# DP0507-1A0.net
KiCad netlist of a schematic drawn in Altium Designer
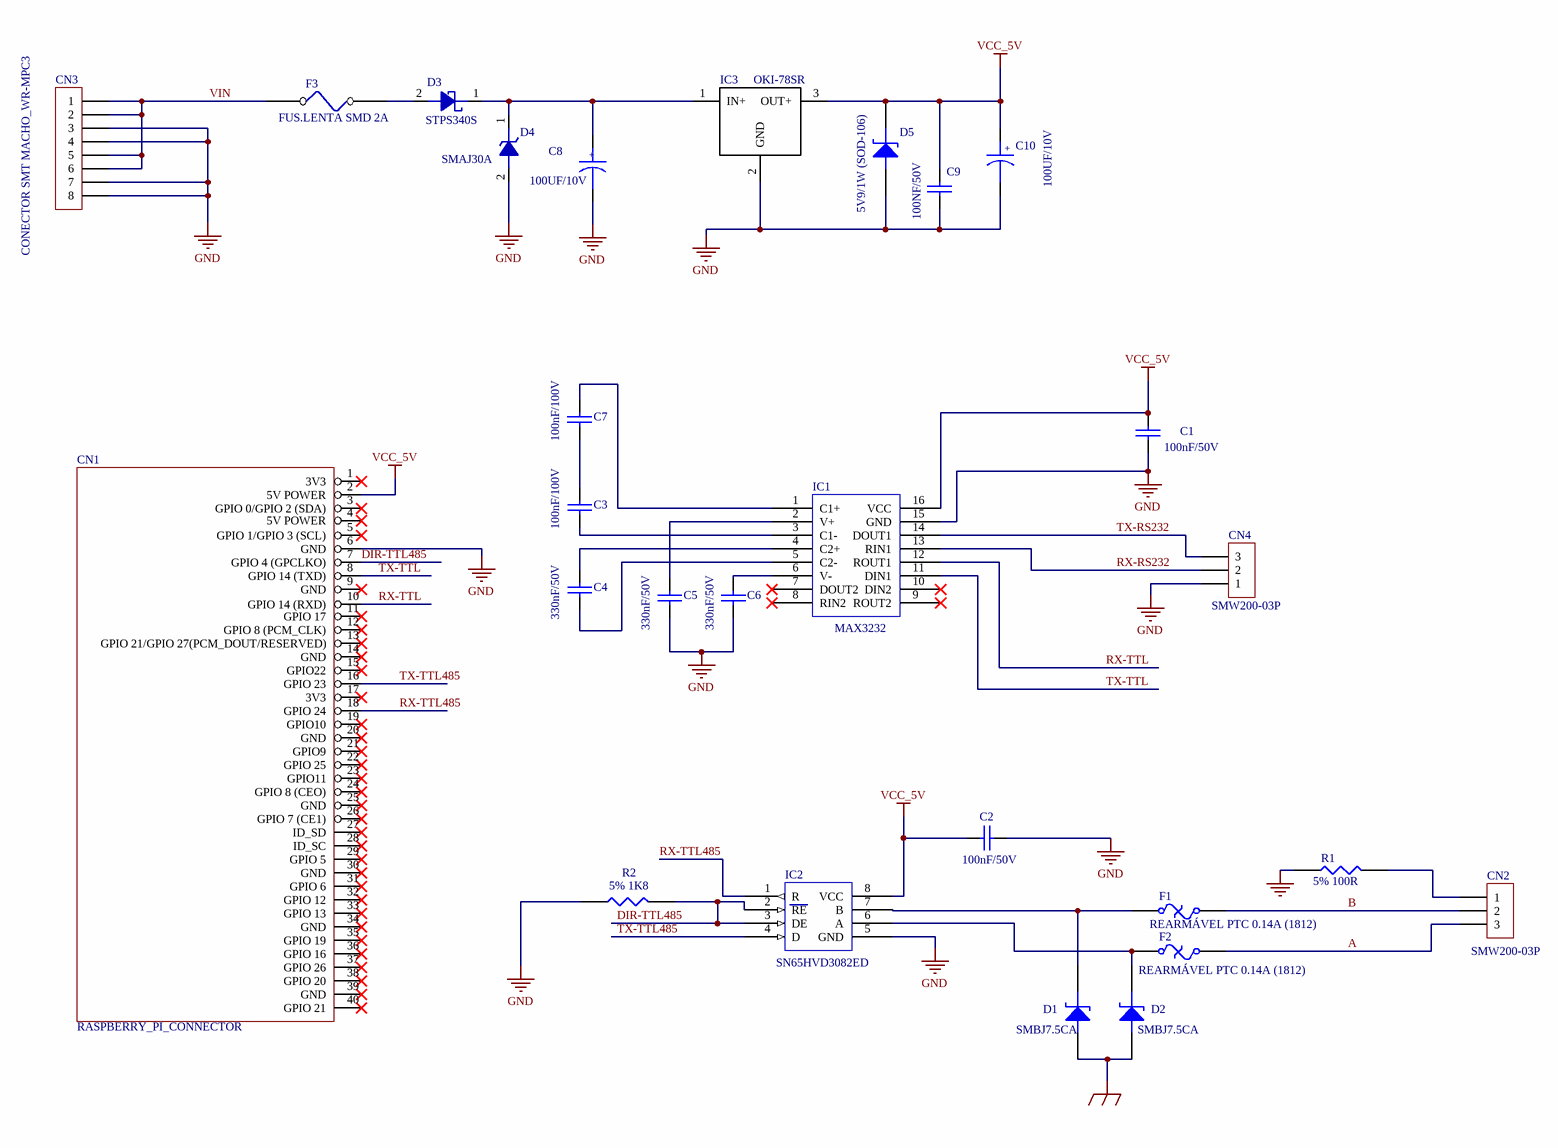
[diagram p0: DP0507-1A0.SchDoc]

(export (version "E")
  (design (tool "Eeschema 10.0.6"))
  (components
    (comp (ref "C1")
      (value "B217602")
      (footprint "C0805")
      (description "COND. CERAMICO SMD 10% 100NF (0805) 50V")
      (fields (field (name "ALTIUM_UNNAMED_1") "100nF/50V"))
      (libsource (lib "LIBRARIAS_DMS_SCH") (part "CAP"))
    )
    (comp (ref "C2")
      (value "B217602")
      (footprint "C0805")
      (description "COND. CERAMICO SMD 10% 100NF (0805) 50V")
      (fields (field (name "ALTIUM_UNNAMED_1") "100nF/50V"))
      (libsource (lib "LIBRARIAS_DMS_SCH") (part "CAP"))
    )
    (comp (ref "C3")
      (value "B217613")
      (footprint "C0805")
      (description "COND. CERAMICO SMD 10% 100NF (0805) 100V")
      (fields (field (name "VALOR") "100nF/100V"))
      (libsource (lib "LIBRARIAS_DMS_SCH") (part "CAP"))
    )
    (comp (ref "C4")
      (value "B217631")
      (footprint "C0805")
      (description "COND. CERAMICO SMD 330NF (0805) 50V")
      (fields (field (name "ALTIUM_UNNAMED_1") "330nF/50V"))
      (libsource (lib "LIBRARIAS_DMS_SCH") (part "CAP"))
    )
    (comp (ref "C5")
      (value "B217631")
      (footprint "C0805")
      (description "COND. CERAMICO SMD 330NF (0805) 50V")
      (fields (field (name "ALTIUM_UNNAMED_1") "330nF/50V"))
      (libsource (lib "LIBRARIAS_DMS_SCH") (part "CAP"))
    )
    (comp (ref "C6")
      (value "B217631")
      (footprint "C0805")
      (description "COND. CERAMICO SMD 330NF (0805) 50V")
      (fields (field (name "ALTIUM_UNNAMED_1") "330nF/50V"))
      (libsource (lib "LIBRARIAS_DMS_SCH") (part "CAP"))
    )
    (comp (ref "C7")
      (value "B217613")
      (footprint "C0805")
      (description "COND. CERAMICO SMD 10% 100NF (0805) 100V")
      (fields (field (name "VALOR") "100nF/100V"))
      (libsource (lib "LIBRARIAS_DMS_SCH") (part "CAP"))
    )
    (comp (ref "C8")
      (value "B217600")
      (footprint "LIBRARIAS DMS_PCB:COND ELECT SMD CASE C (TANTALO SMD 100UF/10V)")
      (description "COND. TANTALO SMD 100UF/10V, LOW ESR 10% (2312)")
      (fields (field (name "VALOR") "100UF/10V"))
      (libsource (lib "LIBRARIAS_MICRO_SCH_br") (part "COND. ELECTR. VERT. 220UF/63V"))
    )
    (comp (ref "C9")
      (value "B217602")
      (footprint "LIBRARIAS DMS_PCB:C0805")
      (description "COND. CERAMICO SMD 10% 100NF (0805) 50V")
      (fields (field (name "VALOR") "100NF/50V"))
      (libsource (lib "LIBRARIAS_MICRO_SCH_br") (part "COND. CERAMICO SMD 10% 100NF (0805) 50V"))
    )
    (comp (ref "C10")
      (value "B217600")
      (footprint "LIBRARIAS DMS_PCB:COND ELECT SMD CASE C (TANTALO SMD 100UF/10V)")
      (description "COND. TANTALO SMD 100UF/10V, LOW ESR 10% (2312)")
      (fields (field (name "VALOR") "100UF/10V"))
      (libsource (lib "") (part "COND. ELECTR. VERT. 220UF/63V_1"))
    )
    (comp (ref "CN1")
      (value "E215527")
      (footprint "LIBRARIAS DMS_PCB:SMT DUAL SOCKET HEADER BOTTOM (WR-PHD)_2X20PINS")
      (description "CONECTOR 2X20 PINOS SMD DP2,54MM")
      (fields (field (name "VALOR") "RASPBERRY_PI_CONNECTOR"))
      (libsource (lib "LIBRARIAS_DMS_SCH") (part "RASPBERRY_PI_CONNECTOR"))
    )
    (comp (ref "CN2")
      (value "E215366")
      (footprint "LIBRARIAS DMS_PCB:MOLEX-3PINOS-MACHO a 90 graus")
      (description "CONECTOR 3P SMW200-03P (FOR PCB)")
      (fields (field (name "VALOR") "SMW200-03P"))
      (libsource (lib "") (part "CON3_1"))
    )
    (comp (ref "CN3")
      (value "---TBD---")
      (footprint "LIBRARIAS DMS_PCB:CONECTOR SMT MACHO_WR-MPC3_WURTH_8 pinos")
      (description "CONECTOR SMT MACHO_WR-MPC3_WURTH_8 pinos")
      (fields (field (name "VALOR") "CONECTOR SMT MACHO_WR-MPC3"))
      (libsource (lib "LIBRARIAS_DMS_SCH") (part "CON8"))
    )
    (comp (ref "CN4")
      (value "E215366")
      (footprint "LIBRARIAS DMS_PCB:MOLEX-3PINOS-MACHO a 90 graus")
      (description "CONECTOR 3P SMW200-03P (FOR PCB)")
      (fields (field (name "VALOR") "SMW200-03P"))
      (libsource (lib "LIBRARIAS_MICRO_SCH") (part "CON3"))
    )
    (comp (ref "D1")
      (value "SMBJ7.5CA")
      (footprint "SMB (SMBJ7.5CA)")
      (description "DIODO SMD SMBJ7.5CA")
      (libsource (lib "*") (part "DIODO SMD SMBJ7.5CA"))
    )
    (comp (ref "D2")
      (value "SMBJ7.5CA")
      (footprint "SMB (SMBJ7.5CA)")
      (description "DIODO SMD SMBJ7.5CA")
      (libsource (lib "*") (part "DIODO SMD SMBJ7.5CA"))
    )
    (comp (ref "D3")
      (value "A120500")
      (footprint "LIBRARIAS DMS_PCB:DO214AB (SMC) - STPS340S")
      (description "DIODO SCHOTTKY SMD STPS340S")
      (fields (field (name "VALOR") "STPS340S"))
      (libsource (lib "LIBRARIAS_MICRO_SCH_2009") (part "DIODE SCHOTTKY"))
    )
    (comp (ref "D4")
      (value "A102150")
      (footprint "LIBRARIAS DMS_PCB:DO214AC (SMA)")
      (description "DIODO TRANS-ZORB SMAJ30A")
      (fields (field (name "VALOR") "SMAJ30A"))
      (libsource (lib "DP0235-0A0") (part "DIODE ZENER"))
    )
    (comp (ref "D5")
      (value "A129614")
      (footprint "LIBRARIAS DMS_PCB:SOD-106")
      (description "DIODO ZENER SMD 5V6/1W (SOD-106)")
      (fields (field (name "VALOR") "5V9/1W (SOD-106)"))
      (libsource (lib "LIBRARIAS_MICRO_SCH_br") (part "DIODO ZENER 5V6/1W"))
    )
    (comp (ref "F1")
      (value "D616404")
      (footprint "1812")
      (description "FUSIVEL FUS.LENTA SMD REARMÁVEL PTC 0.14A (1812)")
      (fields (field (name "VALOR") "REARMÁVEL PTC 0.14A (1812)"))
      (libsource (lib "*") (part "Fuse Thermal"))
    )
    (comp (ref "F2")
      (value "D616404")
      (footprint "1812")
      (description "FUSIVEL FUS.LENTA SMD REARMÁVEL PTC 0.14A (1812)")
      (fields (field (name "VALOR") "REARMÁVEL PTC 0.14A (1812)"))
      (libsource (lib "*") (part "Fuse Thermal"))
    )
    (comp (ref "F3")
      (value "D616400")
      (footprint "LIBRARIAS DMS_PCB:R1206")
      (description "FUSIVEL FUS.LENTA SMD 2A")
      (fields (field (name "VALOR") "FUS.LENTA SMD 2A"))
      (libsource (lib "LIBRARIAS_MICRO_SCH_2009") (part "FUSIVEL FUS.LENTA SMD 2A"))
    )
    (comp (ref "IC1")
      (value "MAX3232 (SOIC-16)")
      (footprint "LIBRARIAS DMS_PCB:SOIC-16 (MAX3232)")
      (description "C.I. SMD MAX3232")
      (fields (field (name "VALOR") "MAX3232"))
      (libsource (lib "LIBRARIAS_DMS_SCH") (part "MAX3232 (SOIC-16)"))
    )
    (comp (ref "IC2")
      (value "SN65HVD3082")
      (footprint "LIBRARIAS DMS_PCB:PSOP-8")
      (description "INTEGRADO 8 PINOS SMD - SN65HVD3082ED")
      (fields (field (name "VALOR") "SN65HVD3082ED"))
      (libsource (lib "LIBRARIAS_DMS_SCH") (part "SN65HVD3082"))
    )
    (comp (ref "IC3")
      (value "C110035")
      (footprint "LIBRARIAS DMS_PCB:OKI-78SR (TO-220)")
      (description "CONVERSOR DC/DC OKI-78SR")
      (fields (field (name "VALOR") "OKI-78SR"))
      (libsource (lib "LIBRARIAS_MICRO_SCH_br") (part "OKI-78SR (TO-220)"))
    )
    (comp (ref "R1")
      (value "B306009")
      (footprint "R0805")
      (description "RESISTÊNCIA SMD")
      (fields (field (name "VALOR") "5% 100R"))
      (libsource (lib "*") (part "RESISTENCIA SMD"))
    )
    (comp (ref "R2")
      (value "B306004")
      (footprint "R0805")
      (description "RESISTENCIA SMD 5% 1K8 (0805)")
      (fields (field (name "VALOR") "5% 1K8"))
      (libsource (lib "LIBRARIAS_DMS_SCH") (part "RESISTENCIA SMD 5% 1K8 (0805)"))
    )
  )
  (nets
    (net (code "1") (name "/A") (class "Default")
      (node (ref "CN2") (pin "3") (pinfunction "3_3") (pintype "passive"))
      (node (ref "F2") (pin "2") (pinfunction "2_2") (pintype "passive"))
    )
    (net (code "2") (name "/B") (class "Default")
      (node (ref "CN2") (pin "2") (pinfunction "2_2") (pintype "passive"))
      (node (ref "F1") (pin "2") (pinfunction "2_2") (pintype "passive"))
    )
    (net (code "3") (name "/DIR-TTL485") (class "Default")
      (node (ref "CN1") (pin "7") (pinfunction "GPIO_4_(GPCLKO)_7") (pintype "passive"))
      (node (ref "IC2") (pin "2") (pinfunction "RE_2") (pintype "input"))
      (node (ref "IC2") (pin "3") (pinfunction "DE_3") (pintype "input"))
      (node (ref "R2") (pin "2") (pinfunction "2_2") (pintype "passive"))
    )
    (net (code "4") (name "/RX-RS232") (class "Default")
      (node (ref "CN4") (pin "2") (pinfunction "2_2") (pintype "passive"))
      (node (ref "IC1") (pin "13") (pinfunction "RIN1_13") (pintype "passive"))
    )
    (net (code "5") (name "/RX-TTL") (class "Default")
      (node (ref "CN1") (pin "10") (pinfunction "GPIO_14_(RXD)_10") (pintype "passive"))
      (node (ref "IC1") (pin "12") (pinfunction "ROUT1_12") (pintype "passive"))
    )
    (net (code "6") (name "/RX-TTL485") (class "Default")
      (node (ref "CN1") (pin "18") (pinfunction "GPIO_24_18") (pintype "passive"))
      (node (ref "IC2") (pin "1") (pinfunction "R_1") (pintype "output"))
    )
    (net (code "7") (name "/TX-RS232") (class "Default")
      (node (ref "CN4") (pin "3") (pinfunction "3_3") (pintype "passive"))
      (node (ref "IC1") (pin "14") (pinfunction "DOUT1_14") (pintype "passive"))
    )
    (net (code "8") (name "/TX-TTL") (class "Default")
      (node (ref "CN1") (pin "8") (pinfunction "GPIO_14_(TXD)_8") (pintype "passive"))
      (node (ref "IC1") (pin "11") (pinfunction "DIN1_11") (pintype "passive"))
    )
    (net (code "9") (name "/TX-TTL485") (class "Default")
      (node (ref "CN1") (pin "16") (pinfunction "GPIO_23_16") (pintype "passive"))
      (node (ref "IC2") (pin "4") (pinfunction "D_4") (pintype "input"))
    )
    (net (code "10") (name "/VIN") (class "Default")
      (node (ref "CN3") (pin "1") (pinfunction "1_1") (pintype "passive"))
      (node (ref "CN3") (pin "2") (pinfunction "2_2") (pintype "passive"))
      (node (ref "CN3") (pin "5") (pinfunction "5_5") (pintype "passive"))
      (node (ref "CN3") (pin "6") (pinfunction "6_6") (pintype "passive"))
      (node (ref "F3") (pin "2") (pinfunction "2_2") (pintype "passive"))
    )
    (net (code "11") (name "EARTH") (class "Default")
      (node (ref "D1") (pin "2") (pinfunction "A_2") (pintype "passive"))
      (node (ref "D2") (pin "2") (pinfunction "A_2") (pintype "passive"))
    )
    (net (code "12") (name "GND") (class "Default")
      (node (ref "C1") (pin "2") (pinfunction "2_2") (pintype "passive"))
      (node (ref "C10") (pin "2") (pinfunction "2_2") (pintype "passive"))
      (node (ref "C2") (pin "2") (pinfunction "2_2") (pintype "passive"))
      (node (ref "C5") (pin "2") (pinfunction "2_2") (pintype "passive"))
      (node (ref "C6") (pin "2") (pinfunction "2_2") (pintype "passive"))
      (node (ref "C8") (pin "2") (pinfunction "2_2") (pintype "passive"))
      (node (ref "C9") (pin "2") (pinfunction "2_2") (pintype "passive"))
      (node (ref "CN1") (pin "6") (pinfunction "GND_6") (pintype "passive"))
      (node (ref "CN3") (pin "3") (pinfunction "3_3") (pintype "passive"))
      (node (ref "CN3") (pin "4") (pinfunction "4_4") (pintype "passive"))
      (node (ref "CN3") (pin "7") (pinfunction "7_7") (pintype "passive"))
      (node (ref "CN3") (pin "8") (pinfunction "8_8") (pintype "passive"))
      (node (ref "CN4") (pin "1") (pinfunction "1_1") (pintype "passive"))
      (node (ref "D4") (pin "2") (pinfunction "ANODE_2") (pintype "passive"))
      (node (ref "D5") (pin "2") (pinfunction "A_2") (pintype "passive"))
      (node (ref "IC1") (pin "15") (pinfunction "GND_15") (pintype "power_in"))
      (node (ref "IC2") (pin "5") (pinfunction "GND_5") (pintype "power_in"))
      (node (ref "IC3") (pin "2") (pinfunction "GND_2") (pintype "power_in"))
      (node (ref "R1") (pin "1") (pinfunction "1_1") (pintype "passive"))
      (node (ref "R2") (pin "1") (pinfunction "1_1") (pintype "passive"))
    )
    (net (code "13") (name "Net-(C3-Pad1)") (class "Default")
      (node (ref "C3") (pin "1") (pinfunction "1_1") (pintype "passive"))
      (node (ref "C7") (pin "2") (pinfunction "2_2") (pintype "passive"))
    )
    (net (code "14") (name "Net-(CN2-Pad1)") (class "Default")
      (node (ref "CN2") (pin "1") (pinfunction "1_1") (pintype "passive"))
      (node (ref "R1") (pin "2") (pinfunction "2_2") (pintype "passive"))
    )
    (net (code "15") (name "Net-(D1-K)") (class "Default")
      (node (ref "D1") (pin "1") (pinfunction "K_1") (pintype "passive"))
      (node (ref "F1") (pin "1") (pinfunction "1_1") (pintype "passive"))
      (node (ref "IC2") (pin "7") (pinfunction "B_7") (pintype "tri_state"))
    )
    (net (code "16") (name "Net-(D2-K)") (class "Default")
      (node (ref "D2") (pin "1") (pinfunction "K_1") (pintype "passive"))
      (node (ref "F2") (pin "1") (pinfunction "1_1") (pintype "passive"))
      (node (ref "IC2") (pin "6") (pinfunction "A_6") (pintype "tri_state"))
    )
    (net (code "17") (name "Net-(D3-ANODE)") (class "Default")
      (node (ref "D3") (pin "2") (pinfunction "ANODE_2") (pintype "passive"))
      (node (ref "F3") (pin "1") (pinfunction "1_1") (pintype "passive"))
    )
    (net (code "18") (name "Net-(D3-CATHODE)") (class "Default")
      (node (ref "C8") (pin "1") (pinfunction "1_1") (pintype "passive"))
      (node (ref "D3") (pin "1") (pinfunction "CATHODE_1") (pintype "passive"))
      (node (ref "D4") (pin "1") (pinfunction "CATHODE_1") (pintype "passive"))
      (node (ref "IC3") (pin "1") (pinfunction "IN+_1") (pintype "passive"))
    )
    (net (code "19") (name "Net-(IC1-C1+)") (class "Default")
      (node (ref "C7") (pin "1") (pinfunction "1_1") (pintype "passive"))
      (node (ref "IC1") (pin "1") (pinfunction "C1+_1") (pintype "passive"))
    )
    (net (code "20") (name "Net-(IC1-C1-)") (class "Default")
      (node (ref "C3") (pin "2") (pinfunction "2_2") (pintype "passive"))
      (node (ref "IC1") (pin "3") (pinfunction "C1-_3") (pintype "passive"))
    )
    (net (code "21") (name "Net-(IC1-C2+)") (class "Default")
      (node (ref "C4") (pin "1") (pinfunction "1_1") (pintype "passive"))
      (node (ref "IC1") (pin "4") (pinfunction "C2+_4") (pintype "passive"))
    )
    (net (code "22") (name "Net-(IC1-C2-)") (class "Default")
      (node (ref "C4") (pin "2") (pinfunction "2_2") (pintype "passive"))
      (node (ref "IC1") (pin "5") (pinfunction "C2-_5") (pintype "passive"))
    )
    (net (code "23") (name "Net-(IC1-V+)") (class "Default")
      (node (ref "C5") (pin "1") (pinfunction "1_1") (pintype "passive"))
      (node (ref "IC1") (pin "2") (pinfunction "V+_2") (pintype "power_in"))
    )
    (net (code "24") (name "Net-(IC1-V-)") (class "Default")
      (node (ref "C6") (pin "1") (pinfunction "1_1") (pintype "passive"))
      (node (ref "IC1") (pin "6") (pinfunction "V-_6") (pintype "power_in"))
    )
    (net (code "25") (name "VCC_5V") (class "Default")
      (node (ref "C1") (pin "1") (pinfunction "1_1") (pintype "passive"))
      (node (ref "C10") (pin "1") (pinfunction "1_1") (pintype "passive"))
      (node (ref "C2") (pin "1") (pinfunction "1_1") (pintype "passive"))
      (node (ref "C9") (pin "1") (pinfunction "1_1") (pintype "passive"))
      (node (ref "CN1") (pin "2") (pinfunction "5V_POWER_2") (pintype "passive"))
      (node (ref "D5") (pin "1") (pinfunction "K_1") (pintype "passive"))
      (node (ref "IC1") (pin "16") (pinfunction "VCC_16") (pintype "power_in"))
      (node (ref "IC2") (pin "8") (pinfunction "VCC_8") (pintype "power_in"))
      (node (ref "IC3") (pin "3") (pinfunction "OUT+_3") (pintype "passive"))
    )
    (net (code "26") (name "unconnected-(CN1-3V3-Pad1)") (class "Default")
      (node (ref "CN1") (pin "1") (pinfunction "3V3_1") (pintype "passive+no_connect"))
    )
    (net (code "27") (name "unconnected-(CN1-3V3-Pad17)") (class "Default")
      (node (ref "CN1") (pin "17") (pinfunction "3V3_17") (pintype "passive+no_connect"))
    )
    (net (code "28") (name "unconnected-(CN1-5V_POWER-Pad4)") (class "Default")
      (node (ref "CN1") (pin "4") (pinfunction "5V_POWER_4") (pintype "passive+no_connect"))
    )
    (net (code "29") (name "unconnected-(CN1-GND-Pad9)") (class "Default")
      (node (ref "CN1") (pin "9") (pinfunction "GND_9") (pintype "passive+no_connect"))
    )
    (net (code "30") (name "unconnected-(CN1-GND-Pad14)") (class "Default")
      (node (ref "CN1") (pin "14") (pinfunction "GND_14") (pintype "passive+no_connect"))
    )
    (net (code "31") (name "unconnected-(CN1-GND-Pad20)") (class "Default")
      (node (ref "CN1") (pin "20") (pinfunction "GND_20") (pintype "passive+no_connect"))
    )
    (net (code "32") (name "unconnected-(CN1-GND-Pad25)") (class "Default")
      (node (ref "CN1") (pin "25") (pinfunction "GND_25") (pintype "passive+no_connect"))
    )
    (net (code "33") (name "unconnected-(CN1-GND-Pad30)") (class "Default")
      (node (ref "CN1") (pin "30") (pinfunction "GND_30") (pintype "passive+no_connect"))
    )
    (net (code "34") (name "unconnected-(CN1-GND-Pad34)") (class "Default")
      (node (ref "CN1") (pin "34") (pinfunction "GND_34") (pintype "passive+no_connect"))
    )
    (net (code "35") (name "unconnected-(CN1-GND-Pad39)") (class "Default")
      (node (ref "CN1") (pin "39") (pinfunction "GND_39") (pintype "passive+no_connect"))
    )
    (net (code "36") (name "unconnected-(CN1-GPIO9-Pad21)") (class "Default")
      (node (ref "CN1") (pin "21") (pinfunction "GPIO9_21") (pintype "passive+no_connect"))
    )
    (net (code "37") (name "unconnected-(CN1-GPIO10-Pad19)") (class "Default")
      (node (ref "CN1") (pin "19") (pinfunction "GPIO10_19") (pintype "passive+no_connect"))
    )
    (net (code "38") (name "unconnected-(CN1-GPIO11-Pad23)") (class "Default")
      (node (ref "CN1") (pin "23") (pinfunction "GPIO11_23") (pintype "passive+no_connect"))
    )
    (net (code "39") (name "unconnected-(CN1-GPIO22-Pad15)") (class "Default")
      (node (ref "CN1") (pin "15") (pinfunction "GPIO22_15") (pintype "passive+no_connect"))
    )
    (net (code "40") (name "unconnected-(CN1-GPIO_0{slash}GPIO_2_(SDA)-Pad3)") (class "Default")
      (node (ref "CN1") (pin "3") (pinfunction "GPIO_0/GPIO_2_(SDA)_3") (pintype "passive+no_connect"))
    )
    (net (code "41") (name "unconnected-(CN1-GPIO_1{slash}GPIO_3_(SCL)-Pad5)") (class "Default")
      (node (ref "CN1") (pin "5") (pinfunction "GPIO_1/GPIO_3_(SCL)_5") (pintype "passive+no_connect"))
    )
    (net (code "42") (name "unconnected-(CN1-GPIO_5-Pad29)") (class "Default")
      (node (ref "CN1") (pin "29") (pinfunction "GPIO_5_29") (pintype "passive+no_connect"))
    )
    (net (code "43") (name "unconnected-(CN1-GPIO_6-Pad31)") (class "Default")
      (node (ref "CN1") (pin "31") (pinfunction "GPIO_6_31") (pintype "passive+no_connect"))
    )
    (net (code "44") (name "unconnected-(CN1-GPIO_7_(CE1)-Pad26)") (class "Default")
      (node (ref "CN1") (pin "26") (pinfunction "GPIO_7_(CE1)_26") (pintype "passive+no_connect"))
    )
    (net (code "45") (name "unconnected-(CN1-GPIO_8_(CEO)-Pad24)") (class "Default")
      (node (ref "CN1") (pin "24") (pinfunction "GPIO_8_(CEO)_24") (pintype "passive+no_connect"))
    )
    (net (code "46") (name "unconnected-(CN1-GPIO_8_(PCM_CLK)-Pad12)") (class "Default")
      (node (ref "CN1") (pin "12") (pinfunction "GPIO_8_(PCM_CLK)_12") (pintype "passive+no_connect"))
    )
    (net (code "47") (name "unconnected-(CN1-GPIO_12-Pad32)") (class "Default")
      (node (ref "CN1") (pin "32") (pinfunction "GPIO_12_32") (pintype "passive+no_connect"))
    )
    (net (code "48") (name "unconnected-(CN1-GPIO_13-Pad33)") (class "Default")
      (node (ref "CN1") (pin "33") (pinfunction "GPIO_13_33") (pintype "passive+no_connect"))
    )
    (net (code "49") (name "unconnected-(CN1-GPIO_16-Pad36)") (class "Default")
      (node (ref "CN1") (pin "36") (pinfunction "GPIO_16_36") (pintype "passive+no_connect"))
    )
    (net (code "50") (name "unconnected-(CN1-GPIO_17-Pad11)") (class "Default")
      (node (ref "CN1") (pin "11") (pinfunction "GPIO_17_11") (pintype "passive+no_connect"))
    )
    (net (code "51") (name "unconnected-(CN1-GPIO_19-Pad35)") (class "Default")
      (node (ref "CN1") (pin "35") (pinfunction "GPIO_19_35") (pintype "passive+no_connect"))
    )
    (net (code "52") (name "unconnected-(CN1-GPIO_20-Pad38)") (class "Default")
      (node (ref "CN1") (pin "38") (pinfunction "GPIO_20_38") (pintype "passive+no_connect"))
    )
    (net (code "53") (name "unconnected-(CN1-GPIO_21-Pad40)") (class "Default")
      (node (ref "CN1") (pin "40") (pinfunction "GPIO_21_40") (pintype "passive+no_connect"))
    )
    (net (code "54") (name "unconnected-(CN1-GPIO_21{slash}GPIO_27(PCM_DOUT{slash}RESERVED)-Pad13)") (class "Default")
      (node (ref "CN1") (pin "13") (pinfunction "GPIO_21/GPIO_27(PCM_DOUT/RESERVED)_13") (pintype "passive+no_connect"))
    )
    (net (code "55") (name "unconnected-(CN1-GPIO_25-Pad22)") (class "Default")
      (node (ref "CN1") (pin "22") (pinfunction "GPIO_25_22") (pintype "passive+no_connect"))
    )
    (net (code "56") (name "unconnected-(CN1-GPIO_26-Pad37)") (class "Default")
      (node (ref "CN1") (pin "37") (pinfunction "GPIO_26_37") (pintype "passive+no_connect"))
    )
    (net (code "57") (name "unconnected-(CN1-ID_SC-Pad28)") (class "Default")
      (node (ref "CN1") (pin "28") (pinfunction "ID_SC_28") (pintype "passive+no_connect"))
    )
    (net (code "58") (name "unconnected-(CN1-ID_SD-Pad27)") (class "Default")
      (node (ref "CN1") (pin "27") (pinfunction "ID_SD_27") (pintype "passive+no_connect"))
    )
    (net (code "59") (name "unconnected-(IC1-DIN2-Pad10)") (class "Default")
      (node (ref "IC1") (pin "10") (pinfunction "DIN2_10") (pintype "passive+no_connect"))
    )
    (net (code "60") (name "unconnected-(IC1-DOUT2-Pad7)") (class "Default")
      (node (ref "IC1") (pin "7") (pinfunction "DOUT2_7") (pintype "passive+no_connect"))
    )
    (net (code "61") (name "unconnected-(IC1-RIN2-Pad8)") (class "Default")
      (node (ref "IC1") (pin "8") (pinfunction "RIN2_8") (pintype "passive+no_connect"))
    )
    (net (code "62") (name "unconnected-(IC1-ROUT2-Pad9)") (class "Default")
      (node (ref "IC1") (pin "9") (pinfunction "ROUT2_9") (pintype "passive+no_connect"))
    )
  )
)
